# Current_Sensor.net
KiCad netlist of a schematic drawn in Altium Designer
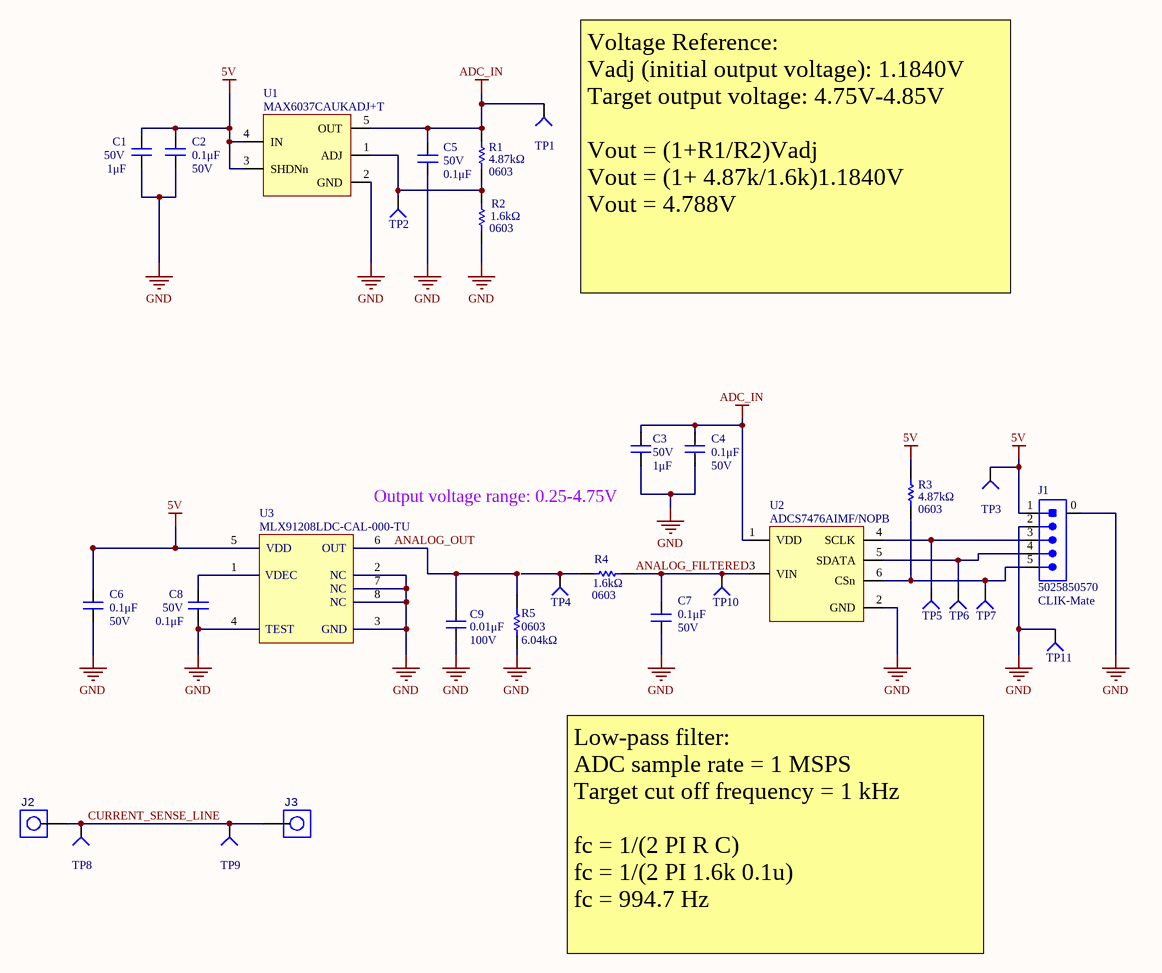
[diagram p0: Current Sensor.SchDoc]

(export (version "E")
  (design (tool "Eeschema 10.0.6"))
  (components
    (comp (ref "C1")
      (value "1μF")
      (footprint "CAP0603")
      (description "CAP CER 1UF 50V X6S 0603")
      (fields (field (name "VOLTAGE RATING") "50V") (field (name "Comment") "CAP_1uF_50V_0603"))
      (libsource (lib "UWRT_Schematic_Library_2020") (part "CAP_1uF_50V_0603"))
    )
    (comp (ref "C2")
      (value "0.1μF")
      (footprint "CAP0603")
      (description "CAP CER 0.1UF 50V X7R 0603")
      (fields (field (name "VOLTAGE RATING") "50V") (field (name "Comment") "CAP_0.1uF_50V_0603"))
      (libsource (lib "UWRT_Schematic_Library_2020") (part "CAP_0.1uF_50V_0603"))
    )
    (comp (ref "C3")
      (value "1μF")
      (footprint "CAP0603")
      (description "CAP CER 1UF 50V X6S 0603")
      (fields (field (name "VOLTAGE RATING") "50V") (field (name "Comment") "CAP_1uF_50V_0603"))
      (libsource (lib "UWRT_Schematic_Library_2020") (part "CAP_1uF_50V_0603"))
    )
    (comp (ref "C4")
      (value "0.1μF")
      (footprint "CAP0603")
      (description "CAP CER 0.1UF 50V X7R 0603")
      (fields (field (name "VOLTAGE RATING") "50V") (field (name "Comment") "CAP_0.1uF_50V_0603"))
      (libsource (lib "UWRT_Schematic_Library_2020") (part "CAP_0.1uF_50V_0603"))
    )
    (comp (ref "C5")
      (value "0.1μF")
      (footprint "CAP0603")
      (description "CAP CER 0.1UF 50V X7R 0603")
      (fields (field (name "VOLTAGE RATING") "50V") (field (name "Comment") "CAP_0.1uF_50V_0603"))
      (libsource (lib "UWRT_Schematic_Library_2020") (part "CAP_0.1uF_50V_0603"))
    )
    (comp (ref "C6")
      (value "0.1μF")
      (footprint "CAP0603")
      (description "CAP CER 0.1UF 50V X7R 0603")
      (fields (field (name "VOLTAGE RATING") "50V") (field (name "Comment") "CAP_0.1uF_50V_0603"))
      (libsource (lib "UWRT_Schematic_Library_2020") (part "CAP_0.1uF_50V_0603"))
    )
    (comp (ref "C7")
      (value "0.1μF")
      (footprint "CAP0603")
      (description "CAP CER 0.1UF 50V X7R 0603")
      (fields (field (name "VOLTAGE RATING") "50V") (field (name "Comment") "CAP_0.1uF_50V_0603"))
      (libsource (lib "UWRT_Schematic_Library_2020") (part "CAP_0.1uF_50V_0603"))
    )
    (comp (ref "C8")
      (value "0.1μF")
      (footprint "CAP0603")
      (description "CAP CER 0.1UF 50V X7R 0603")
      (fields (field (name "VOLTAGE RATING") "50V") (field (name "Comment") "CAP_0.1uF_50V_0603"))
      (libsource (lib "UWRT_Schematic_Library_2020") (part "CAP_0.1uF_50V_0603"))
    )
    (comp (ref "C9")
      (value "0.01μF")
      (footprint "CAP0603")
      (description "CAP CER 10000PF 100V X7R 0603")
      (fields (field (name "VOLTAGE RATING") "100V") (field (name "Comment") "CAP_0.01uF_100V_0603"))
      (libsource (lib "UWRT_Schematic_Library_2020") (part "CAP_0.01uF_100V_0603"))
    )
    (comp (ref "J1")
      (value "CON_5M_SM_RA")
      (footprint "MOLEX-5025850570")
      (description "CONN HEADER SMD RIGHT ANGLE 1.5MM PITCH")
      (fields (field (name "MANUFACTURER PART NUMBER 1") "5025850570") (field (name "FAMILY") "CLIK-Mate"))
      (libsource (lib "UWRT_Schematic_Library_2020") (part "CON_5M_SM_RA"))
    )
    (comp (ref "J2")
      (value "SCREW_TERMINAL_1_POS_6_32")
      (footprint "7701_KEYSTONE")
      (description "TERM W/ASSEMBLD SCREW VERT PCMNT")
      (libsource (lib "UWRT_Schematic_Library_2020") (part "SCREW_TERMINAL_1_POS_6_32"))
    )
    (comp (ref "J3")
      (value "SCREW_TERMINAL_1_POS_6_32")
      (footprint "7701_KEYSTONE")
      (description "TERM W/ASSEMBLD SCREW VERT PCMNT")
      (libsource (lib "UWRT_Schematic_Library_2020") (part "SCREW_TERMINAL_1_POS_6_32"))
    )
    (comp (ref "R1")
      (value "4.87kΩ")
      (footprint "RES0603")
      (description "RES 4.87K OHM 1% 1/8W 0603")
      (fields (field (name "Comment") "RES_4.87kΩ_0603_1%"))
      (libsource (lib "UWRT_Schematic_Library_2020") (part "RES_4.87kΩ_0603_1%"))
    )
    (comp (ref "R2")
      (value "1.6kΩ")
      (footprint "RES0603")
      (description "RES 1.6K OHM 1% 1/4W 0603")
      (fields (field (name "PACKAGE/FOOTPRINT") "0603") (field (name "Comment") "RES_1.6kΩ_0603_1%"))
      (libsource (lib "UWRT_Schematic_Library_2020") (part "RES_1.6kΩ_0603_1%"))
    )
    (comp (ref "R3")
      (value "4.87kΩ")
      (footprint "RES0603")
      (description "RES 4.87K OHM 1% 1/8W 0603")
      (fields (field (name "Comment") "RES_4.87kΩ_0603_1%"))
      (libsource (lib "UWRT_Schematic_Library_2020") (part "RES_4.87kΩ_0603_1%"))
    )
    (comp (ref "R4")
      (value "1.6kΩ")
      (footprint "RES0603")
      (description "RES 1.6K OHM 1% 1/4W 0603")
      (fields (field (name "PACKAGE/FOOTPRINT") "0603") (field (name "Comment") "RES_1.6kΩ_0603_1%"))
      (libsource (lib "UWRT_Schematic_Library_2020") (part "RES_1.6kΩ_0603_1%"))
    )
    (comp (ref "R5")
      (value "6.04kΩ")
      (footprint "RES0603")
      (description "RES 6.04K OHM 1% 1/10W 0603")
      (fields (field (name "PACKAGE/FOOTPRINT") "0603") (field (name "Comment") "RES_6.04kΩ_0603_1%"))
      (libsource (lib "UWRT_Schematic_Library_2020") (part "RES_6.04kΩ_0603_1%"))
    )
    (comp (ref "TP1")
      (value "TESTPOINT_SMD_LOOP")
      (footprint "S1751-46R")
      (description "PC TEST POINT SMD")
      (libsource (lib "UWRT_Schematic_Library_2020") (part "TESTPOINT_SMD_LOOP"))
    )
    (comp (ref "TP2")
      (value "TESTPOINT_1MM_CIRCLE")
      (footprint "TESTPOINT_CIRCLE_1MM")
      (description "TESTPOINT 1MM CIRCLE")
      (libsource (lib "UWRT_Schematic_Library_2020") (part "TESTPOINT_1MM_CIRCLE"))
    )
    (comp (ref "TP3")
      (value "TESTPOINT_SMD_LOOP")
      (footprint "S1751-46R")
      (description "PC TEST POINT SMD")
      (libsource (lib "UWRT_Schematic_Library_2020") (part "TESTPOINT_SMD_LOOP"))
    )
    (comp (ref "TP4")
      (value "TESTPOINT_1MM_CIRCLE")
      (footprint "TESTPOINT_CIRCLE_1MM")
      (description "TESTPOINT 1MM CIRCLE")
      (libsource (lib "UWRT_Schematic_Library_2020") (part "TESTPOINT_1MM_CIRCLE"))
    )
    (comp (ref "TP5")
      (value "TESTPOINT_1MM_CIRCLE")
      (footprint "TESTPOINT_CIRCLE_1MM")
      (description "TESTPOINT 1MM CIRCLE")
      (libsource (lib "UWRT_Schematic_Library_2020") (part "TESTPOINT_1MM_CIRCLE"))
    )
    (comp (ref "TP6")
      (value "TESTPOINT_1MM_CIRCLE")
      (footprint "TESTPOINT_CIRCLE_1MM")
      (description "TESTPOINT 1MM CIRCLE")
      (libsource (lib "UWRT_Schematic_Library_2020") (part "TESTPOINT_1MM_CIRCLE"))
    )
    (comp (ref "TP7")
      (value "TESTPOINT_1MM_CIRCLE")
      (footprint "TESTPOINT_CIRCLE_1MM")
      (description "TESTPOINT 1MM CIRCLE")
      (libsource (lib "UWRT_Schematic_Library_2020") (part "TESTPOINT_1MM_CIRCLE"))
    )
    (comp (ref "TP8")
      (value "TESTPOINT_SMD_LOOP")
      (footprint "S1751-46R")
      (description "PC TEST POINT SMD")
      (libsource (lib "UWRT_Schematic_Library_2020") (part "TESTPOINT_SMD_LOOP"))
    )
    (comp (ref "TP9")
      (value "TESTPOINT_SMD_LOOP")
      (footprint "S1751-46R")
      (description "PC TEST POINT SMD")
      (libsource (lib "UWRT_Schematic_Library_2020") (part "TESTPOINT_SMD_LOOP"))
    )
    (comp (ref "TP10")
      (value "TESTPOINT_1MM_CIRCLE")
      (footprint "TESTPOINT_CIRCLE_1MM")
      (description "TESTPOINT 1MM CIRCLE")
      (libsource (lib "UWRT_Schematic_Library_2020") (part "TESTPOINT_1MM_CIRCLE"))
    )
    (comp (ref "TP11")
      (value "TESTPOINT_1MM_SQUARE")
      (footprint "TESTPOINT_SQUARE_1MM")
      (description "TESTPOINT 1MM SQUARE")
      (libsource (lib "UWRT_Schematic_Library_2020") (part "TESTPOINT_1MM_SQUARE"))
    )
    (comp (ref "U1")
      (value "MAX6037CAUKADJ+T")
      (footprint "SOT23-5")
      (description "IC VREF SERIES 5V 0.5% SOT23-5")
      (fields
        (field (name "TOLERANCE") "0.5%")
        (field (name "MANUFACTURER PART NUMBER 1") "MAX6037CAUKADJ+T")
      )
      (libsource (lib "UWRT_Schematic_Library_2020") (part "MAX6037CAUKADJ+T"))
    )
    (comp (ref "U2")
      (value "ADCS7476AIMF/NOPB")
      (footprint "ADCS747x")
      (description "IC ADC 12BIT SAR SOT23-6")
      (fields (field (name "MANUFACTURER PART NUMBER 1") "ADCS7476AIMF/NOPB"))
      (libsource (lib "UWRT_Schematic_Library_2020") (part "ADCS7476AIMF/NOPB"))
    )
    (comp (ref "U3")
      (value "MLX91208LDC-CAL-000-TU")
      (footprint "8-SOIC_M")
      (description "SENSOR CURRENT HALL 10MT AC/DC")
      (fields (field (name "MANUFACTURER PART NUMBER 1") "MLX91208LDC-CAL-000-TU"))
      (libsource (lib "UWRT_Schematic_Library_2020") (part "MLX91208LDC-CAL-000-TU"))
    )
  )
  (nets
    (net (code "1") (name "/ANALOG_FILTERED") (class "Default")
      (node (ref "C7") (pin "2") (pinfunction "2_2") (pintype "passive"))
      (node (ref "R4") (pin "1") (pinfunction "1_1") (pintype "passive"))
      (node (ref "TP10") (pin "1") (pinfunction "=value_1") (pintype "passive"))
      (node (ref "U2") (pin "3") (pinfunction "VIN_3") (pintype "passive"))
    )
    (net (code "2") (name "/ANALOG_OUT") (class "Default")
      (node (ref "C9") (pin "2") (pinfunction "2_2") (pintype "passive"))
      (node (ref "R5") (pin "2") (pinfunction "2_2") (pintype "passive"))
      (node (ref "U3") (pin "6") (pinfunction "6_6") (pintype "passive"))
    )
    (net (code "3") (name "/CURRENT_SENSE_LINE") (class "Default")
      (node (ref "J2") (pin "1") (pinfunction "1_1") (pintype "passive"))
      (node (ref "J3") (pin "1") (pinfunction "1_1") (pintype "passive"))
      (node (ref "TP8") (pin "1") (pinfunction "=value_1") (pintype "passive"))
      (node (ref "TP9") (pin "1") (pinfunction "=value_1") (pintype "passive"))
    )
    (net (code "4") (name "5V") (class "Default")
      (node (ref "C1") (pin "2") (pinfunction "2_2") (pintype "passive"))
      (node (ref "C2") (pin "2") (pinfunction "2_2") (pintype "passive"))
      (node (ref "C6") (pin "2") (pinfunction "2_2") (pintype "passive"))
      (node (ref "J1") (pin "1") (pinfunction "1_1") (pintype "passive"))
      (node (ref "R3") (pin "2") (pinfunction "2_2") (pintype "passive"))
      (node (ref "TP3") (pin "1") (pinfunction "=value_1") (pintype "passive"))
      (node (ref "U1") (pin "3") (pinfunction "SHDNn_3") (pintype "passive"))
      (node (ref "U1") (pin "4") (pinfunction "IN_4") (pintype "passive"))
      (node (ref "U3") (pin "5") (pinfunction "5_5") (pintype "passive"))
    )
    (net (code "5") (name "ADC_IN") (class "Default")
      (node (ref "C3") (pin "2") (pinfunction "2_2") (pintype "passive"))
      (node (ref "C4") (pin "2") (pinfunction "2_2") (pintype "passive"))
      (node (ref "C5") (pin "2") (pinfunction "2_2") (pintype "passive"))
      (node (ref "R1") (pin "2") (pinfunction "2_2") (pintype "passive"))
      (node (ref "TP1") (pin "1") (pinfunction "=value_1") (pintype "passive"))
      (node (ref "U1") (pin "5") (pinfunction "OUT_5") (pintype "passive"))
      (node (ref "U2") (pin "1") (pinfunction "VDD_1") (pintype "passive"))
    )
    (net (code "6") (name "GND") (class "Default")
      (node (ref "C1") (pin "1") (pinfunction "1_1") (pintype "passive"))
      (node (ref "C2") (pin "1") (pinfunction "1_1") (pintype "passive"))
      (node (ref "C3") (pin "1") (pinfunction "1_1") (pintype "passive"))
      (node (ref "C4") (pin "1") (pinfunction "1_1") (pintype "passive"))
      (node (ref "C5") (pin "1") (pinfunction "1_1") (pintype "passive"))
      (node (ref "C6") (pin "1") (pinfunction "1_1") (pintype "passive"))
      (node (ref "C7") (pin "1") (pinfunction "1_1") (pintype "passive"))
      (node (ref "C8") (pin "1") (pinfunction "1_1") (pintype "passive"))
      (node (ref "C9") (pin "1") (pinfunction "1_1") (pintype "passive"))
      (node (ref "J1") (pin "0") (pinfunction "0_0") (pintype "passive"))
      (node (ref "J1") (pin "2") (pinfunction "2_2") (pintype "passive"))
      (node (ref "R2") (pin "1") (pinfunction "1_1") (pintype "passive"))
      (node (ref "R5") (pin "1") (pinfunction "1_1") (pintype "passive"))
      (node (ref "TP11") (pin "1") (pinfunction "=value_1") (pintype "passive"))
      (node (ref "U1") (pin "2") (pinfunction "GND_2") (pintype "passive"))
      (node (ref "U2") (pin "2") (pinfunction "GND_2") (pintype "passive"))
      (node (ref "U3") (pin "2") (pinfunction "2_2") (pintype "passive"))
      (node (ref "U3") (pin "3") (pinfunction "3_3") (pintype "passive"))
      (node (ref "U3") (pin "4") (pinfunction "4_4") (pintype "passive"))
      (node (ref "U3") (pin "7") (pinfunction "7_7") (pintype "passive"))
      (node (ref "U3") (pin "8") (pinfunction "8_8") (pintype "passive"))
    )
    (net (code "7") (name "Net-(C8-Pad2)") (class "Default")
      (node (ref "C8") (pin "2") (pinfunction "2_2") (pintype "passive"))
      (node (ref "U3") (pin "1") (pinfunction "1_1") (pintype "passive"))
    )
    (net (code "8") (name "Net-(TP2-=value)") (class "Default")
      (node (ref "R1") (pin "1") (pinfunction "1_1") (pintype "passive"))
      (node (ref "R2") (pin "2") (pinfunction "2_2") (pintype "passive"))
      (node (ref "TP2") (pin "1") (pinfunction "=value_1") (pintype "passive"))
      (node (ref "U1") (pin "1") (pinfunction "ADJ_1") (pintype "passive"))
    )
    (net (code "9") (name "Net-(TP4-=value)") (class "Default")
      (node (ref "R4") (pin "2") (pinfunction "2_2") (pintype "passive"))
      (node (ref "TP4") (pin "1") (pinfunction "=value_1") (pintype "passive"))
    )
    (net (code "10") (name "Net-(TP5-=value)") (class "Default")
      (node (ref "J1") (pin "3") (pinfunction "3_3") (pintype "passive"))
      (node (ref "TP5") (pin "1") (pinfunction "=value_1") (pintype "passive"))
      (node (ref "U2") (pin "4") (pinfunction "SCLK_4") (pintype "passive"))
    )
    (net (code "11") (name "Net-(TP6-=value)") (class "Default")
      (node (ref "J1") (pin "4") (pinfunction "4_4") (pintype "passive"))
      (node (ref "TP6") (pin "1") (pinfunction "=value_1") (pintype "passive"))
      (node (ref "U2") (pin "5") (pinfunction "SDATA_5") (pintype "passive"))
    )
    (net (code "12") (name "Net-(TP7-=value)") (class "Default")
      (node (ref "J1") (pin "5") (pinfunction "5_5") (pintype "passive"))
      (node (ref "R3") (pin "1") (pinfunction "1_1") (pintype "passive"))
      (node (ref "TP7") (pin "1") (pinfunction "=value_1") (pintype "passive"))
      (node (ref "U2") (pin "6") (pinfunction "CSn_6") (pintype "passive"))
    )
  )
)
